# Stack_B.net
KiCad netlist of a schematic drawn in Altium Designer
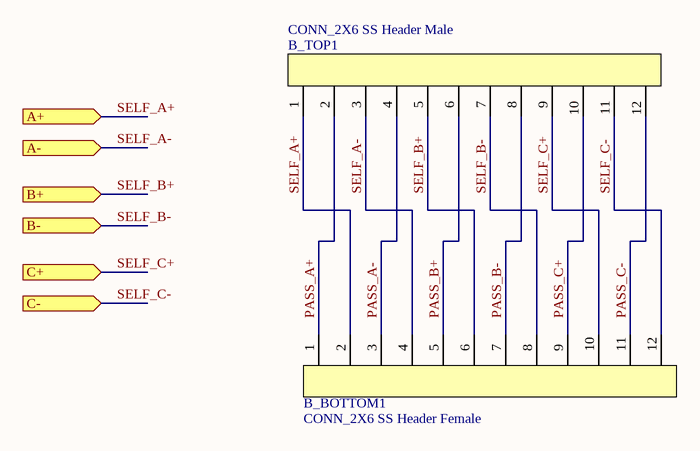
[diagram p0: Stack_B.SchDoc]

(export (version "E")
  (design (tool "Eeschema 10.0.6"))
  (components
    (comp (ref "B_BOTTOM1")
      (value "CONN_2X6 SS Header Female")
      (footprint "SAMTEC_SSW-106-22-F-D-VS")
      (libsource (lib "SSI") (part "CONN_2X6 SS Header"))
    )
    (comp (ref "B_TOP1")
      (value "CONN_2X6 SS Header Male")
      (footprint "SAMTEC_TSM-106-03-F-DV")
      (libsource (lib "") (part "CONN_2X6 SS Header_1"))
    )
  )
  (nets
    (net (code "1") (name "/PASS_A+") (class "Default")
      (node (ref "B_BOTTOM1") (pin "1") (pinfunction "1_1") (pintype "passive"))
      (node (ref "B_TOP1") (pin "2") (pinfunction "2_2") (pintype "passive"))
    )
    (net (code "2") (name "/PASS_A-") (class "Default")
      (node (ref "B_BOTTOM1") (pin "3") (pinfunction "3_3") (pintype "passive"))
      (node (ref "B_TOP1") (pin "4") (pinfunction "4_4") (pintype "passive"))
    )
    (net (code "3") (name "/PASS_B+") (class "Default")
      (node (ref "B_BOTTOM1") (pin "5") (pinfunction "5_5") (pintype "passive"))
      (node (ref "B_TOP1") (pin "6") (pinfunction "6_6") (pintype "passive"))
    )
    (net (code "4") (name "/PASS_B-") (class "Default")
      (node (ref "B_BOTTOM1") (pin "7") (pinfunction "7_7") (pintype "passive"))
      (node (ref "B_TOP1") (pin "8") (pinfunction "8_8") (pintype "passive"))
    )
    (net (code "5") (name "/PASS_C+") (class "Default")
      (node (ref "B_BOTTOM1") (pin "9") (pinfunction "9_9") (pintype "passive"))
      (node (ref "B_TOP1") (pin "10") (pinfunction "10_10") (pintype "passive"))
    )
    (net (code "6") (name "/PASS_C-") (class "Default")
      (node (ref "B_BOTTOM1") (pin "11") (pinfunction "11_11") (pintype "passive"))
      (node (ref "B_TOP1") (pin "12") (pinfunction "12_12") (pintype "passive"))
    )
    (net (code "7") (name "/SELF_A+") (class "Default")
      (node (ref "B_BOTTOM1") (pin "2") (pinfunction "2_2") (pintype "passive"))
      (node (ref "B_TOP1") (pin "1") (pinfunction "1_1") (pintype "passive"))
    )
    (net (code "8") (name "/SELF_A-") (class "Default")
      (node (ref "B_BOTTOM1") (pin "4") (pinfunction "4_4") (pintype "passive"))
      (node (ref "B_TOP1") (pin "3") (pinfunction "3_3") (pintype "passive"))
    )
    (net (code "9") (name "/SELF_B+") (class "Default")
      (node (ref "B_BOTTOM1") (pin "6") (pinfunction "6_6") (pintype "passive"))
      (node (ref "B_TOP1") (pin "5") (pinfunction "5_5") (pintype "passive"))
    )
    (net (code "10") (name "/SELF_B-") (class "Default")
      (node (ref "B_BOTTOM1") (pin "8") (pinfunction "8_8") (pintype "passive"))
      (node (ref "B_TOP1") (pin "7") (pinfunction "7_7") (pintype "passive"))
    )
    (net (code "11") (name "/SELF_C+") (class "Default")
      (node (ref "B_BOTTOM1") (pin "10") (pinfunction "10_10") (pintype "passive"))
      (node (ref "B_TOP1") (pin "9") (pinfunction "9_9") (pintype "passive"))
    )
    (net (code "12") (name "/SELF_C-") (class "Default")
      (node (ref "B_BOTTOM1") (pin "12") (pinfunction "12_12") (pintype "passive"))
      (node (ref "B_TOP1") (pin "11") (pinfunction "11_11") (pintype "passive"))
    )
  )
)
